# ExternSensors.net
KiCad netlist of a schematic drawn in EAGLE
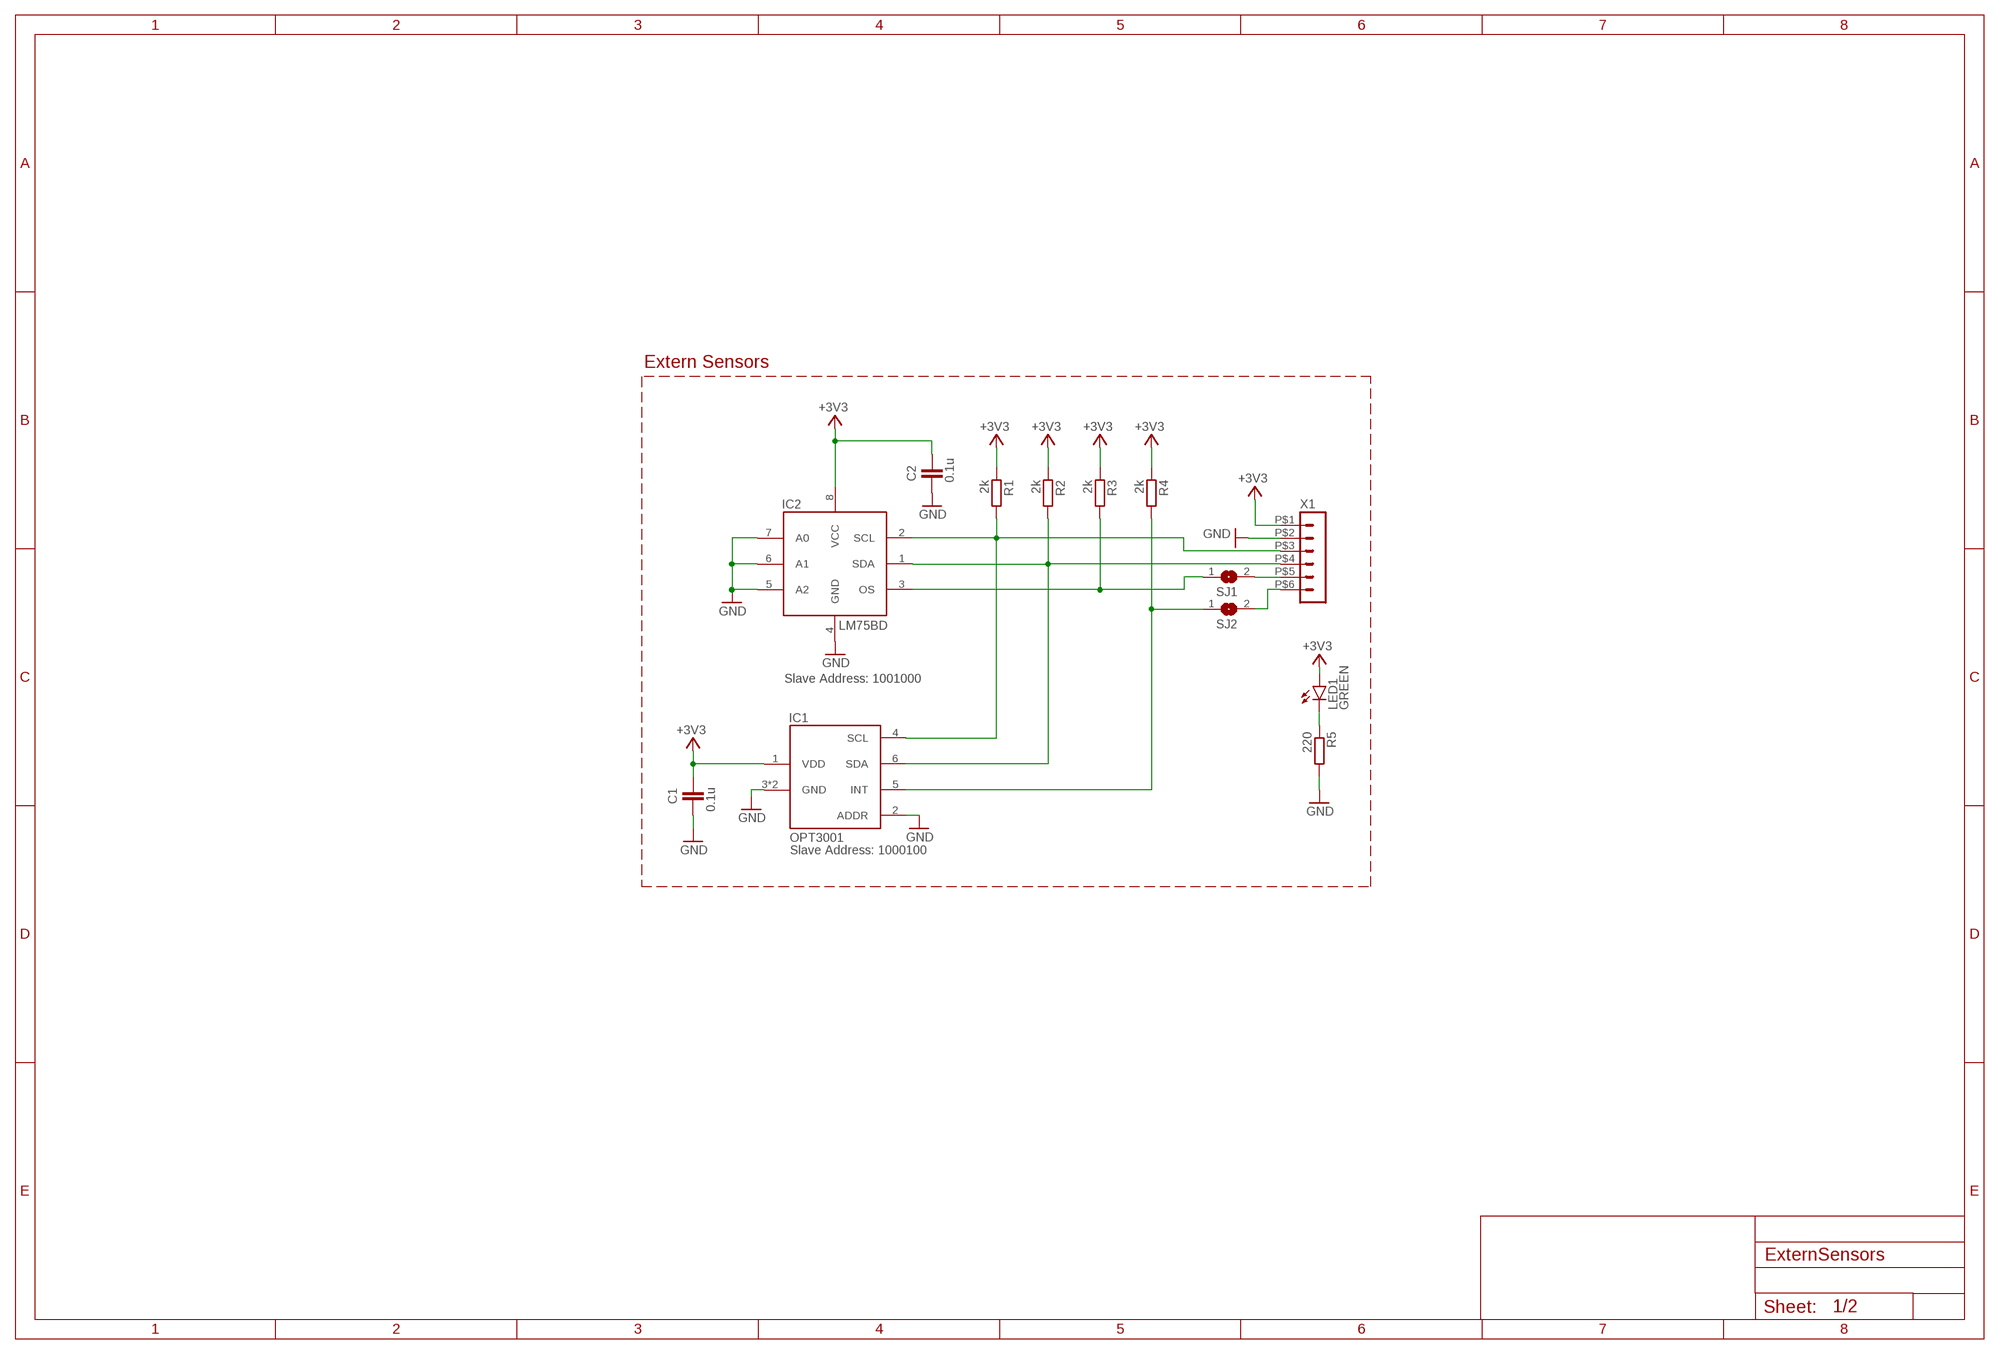
[diagram p0: schematic, sheet 1]

(export (version "E")
  (design (tool "Eeschema 10.0.6"))
  (components
    (comp (ref "C1")
      (value "0.1u")
      (footprint "eagle-import:C0805K")
      (libsource (lib "eagle-import") (part "C-EUC0805K"))
    )
    (comp (ref "C2")
      (value "0.1u")
      (footprint "eagle-import:C0805K")
      (libsource (lib "eagle-import") (part "C-EUC0805K"))
    )
    (comp (ref "IC1")
      (value "OPT3001")
      (footprint "eagle-import:OPT3001")
      (libsource (lib "eagle-import") (part "OPT3001"))
    )
    (comp (ref "IC2")
      (value "LM75BD")
      (footprint "eagle-import:SO8_LM75")
      (libsource (lib "eagle-import") (part "LM75_ICN"))
    )
    (comp (ref "LED1")
      (value "GREEN")
      (footprint "eagle-import:CHIP-LED0805")
      (libsource (lib "eagle-import") (part "LEDCHIP-LED0805"))
    )
    (comp (ref "R1")
      (value "2k")
      (footprint "eagle-import:R0805")
      (libsource (lib "eagle-import") (part "R-EU_R0805"))
    )
    (comp (ref "R2")
      (value "2k")
      (footprint "eagle-import:R0805")
      (libsource (lib "eagle-import") (part "R-EU_R0805"))
    )
    (comp (ref "R3")
      (value "2k")
      (footprint "eagle-import:R0805")
      (libsource (lib "eagle-import") (part "R-EU_R0805"))
    )
    (comp (ref "R4")
      (value "2k")
      (footprint "eagle-import:R0805")
      (libsource (lib "eagle-import") (part "R-EU_R0805"))
    )
    (comp (ref "R5")
      (value "220")
      (footprint "eagle-import:R0805")
      (libsource (lib "eagle-import") (part "R-EU_R0805"))
    )
    (comp (ref "SJ1") (value "SJ") (footprint "eagle-import:SJ") (libsource (lib "eagle-import") (part "SJ")))
    (comp (ref "SJ2") (value "SJ") (footprint "eagle-import:SJ") (libsource (lib "eagle-import") (part "SJ")))
    (comp (ref "X1")
      (value "HEADER_POS6_43650-0612")
      (footprint "eagle-import:43650-0612")
      (libsource (lib "eagle-import") (part "HEADER_POS6_?43650-0612"))
    )
  )
  (nets
    (net (code "1") (name "+3V3") (class "Default")
      (node (ref "C1") (pin "2") (pinfunction "2_2") (pintype "passive"))
      (node (ref "C2") (pin "2") (pinfunction "2_2") (pintype "passive"))
      (node (ref "IC1") (pin "1") (pinfunction "VDD_1") (pintype "power_in"))
      (node (ref "IC2") (pin "8") (pinfunction "VCC_8") (pintype "power_in"))
      (node (ref "LED1") (pin "A") (pinfunction "A_A") (pintype "passive"))
      (node (ref "R1") (pin "1") (pinfunction "1_1") (pintype "passive"))
      (node (ref "R2") (pin "1") (pinfunction "1_1") (pintype "passive"))
      (node (ref "R3") (pin "1") (pinfunction "1_1") (pintype "passive"))
      (node (ref "R4") (pin "1") (pinfunction "1_1") (pintype "passive"))
      (node (ref "X1") (pin "P$1") (pinfunction "1_P$1") (pintype "passive"))
    )
    (net (code "2") (name "GND") (class "Default")
      (node (ref "C1") (pin "1") (pinfunction "1_1") (pintype "passive"))
      (node (ref "C2") (pin "1") (pinfunction "1_1") (pintype "passive"))
      (node (ref "IC1") (pin "2") (pinfunction "ADDR_2") (pintype "bidirectional"))
      (node (ref "IC1") (pin "3") (pinfunction "GND_3") (pintype "power_in"))
      (node (ref "IC1") (pin "P$1") (pinfunction "GND_P$1") (pintype "power_in"))
      (node (ref "IC2") (pin "4") (pinfunction "GND_4") (pintype "power_in"))
      (node (ref "IC2") (pin "5") (pinfunction "A2_5") (pintype "input"))
      (node (ref "IC2") (pin "6") (pinfunction "A1_6") (pintype "input"))
      (node (ref "IC2") (pin "7") (pinfunction "A0_7") (pintype "input"))
      (node (ref "R5") (pin "2") (pinfunction "2_2") (pintype "passive"))
      (node (ref "X1") (pin "P$2") (pinfunction "2_P$2") (pintype "passive"))
    )
    (net (code "3") (name "Net-(IC1-INT)") (class "Default")
      (node (ref "IC1") (pin "5") (pinfunction "INT_5") (pintype "bidirectional"))
      (node (ref "R4") (pin "2") (pinfunction "2_2") (pintype "passive"))
      (node (ref "SJ2") (pin "1") (pinfunction "1_1") (pintype "passive"))
    )
    (net (code "4") (name "Net-(IC1-SCL)") (class "Default")
      (node (ref "IC1") (pin "4") (pinfunction "SCL_4") (pintype "bidirectional"))
      (node (ref "IC2") (pin "2") (pinfunction "SCL_2") (pintype "bidirectional"))
      (node (ref "R1") (pin "2") (pinfunction "2_2") (pintype "passive"))
      (node (ref "X1") (pin "P$3") (pinfunction "3_P$3") (pintype "passive"))
    )
    (net (code "5") (name "Net-(IC1-SDA)") (class "Default")
      (node (ref "IC1") (pin "6") (pinfunction "SDA_6") (pintype "bidirectional"))
      (node (ref "IC2") (pin "1") (pinfunction "SDA_1") (pintype "bidirectional"))
      (node (ref "R2") (pin "2") (pinfunction "2_2") (pintype "passive"))
      (node (ref "X1") (pin "P$4") (pinfunction "4_P$4") (pintype "passive"))
    )
    (net (code "6") (name "Net-(IC2-OS)") (class "Default")
      (node (ref "IC2") (pin "3") (pinfunction "OS_3") (pintype "output"))
      (node (ref "R3") (pin "2") (pinfunction "2_2") (pintype "passive"))
      (node (ref "SJ1") (pin "1") (pinfunction "1_1") (pintype "passive"))
    )
    (net (code "7") (name "Net-(LED1-PadC)") (class "Default")
      (node (ref "LED1") (pin "C") (pinfunction "C_C") (pintype "passive"))
      (node (ref "R5") (pin "1") (pinfunction "1_1") (pintype "passive"))
    )
    (net (code "8") (name "Net-(X1-5)") (class "Default")
      (node (ref "SJ1") (pin "2") (pinfunction "2_2") (pintype "passive"))
      (node (ref "X1") (pin "P$5") (pinfunction "5_P$5") (pintype "passive"))
    )
    (net (code "9") (name "Net-(X1-6)") (class "Default")
      (node (ref "SJ2") (pin "2") (pinfunction "2_2") (pintype "passive"))
      (node (ref "X1") (pin "P$6") (pinfunction "6_P$6") (pintype "passive"))
    )
  )
)
